# MKR1000.net
KiCad netlist of a schematic drawn in EAGLE
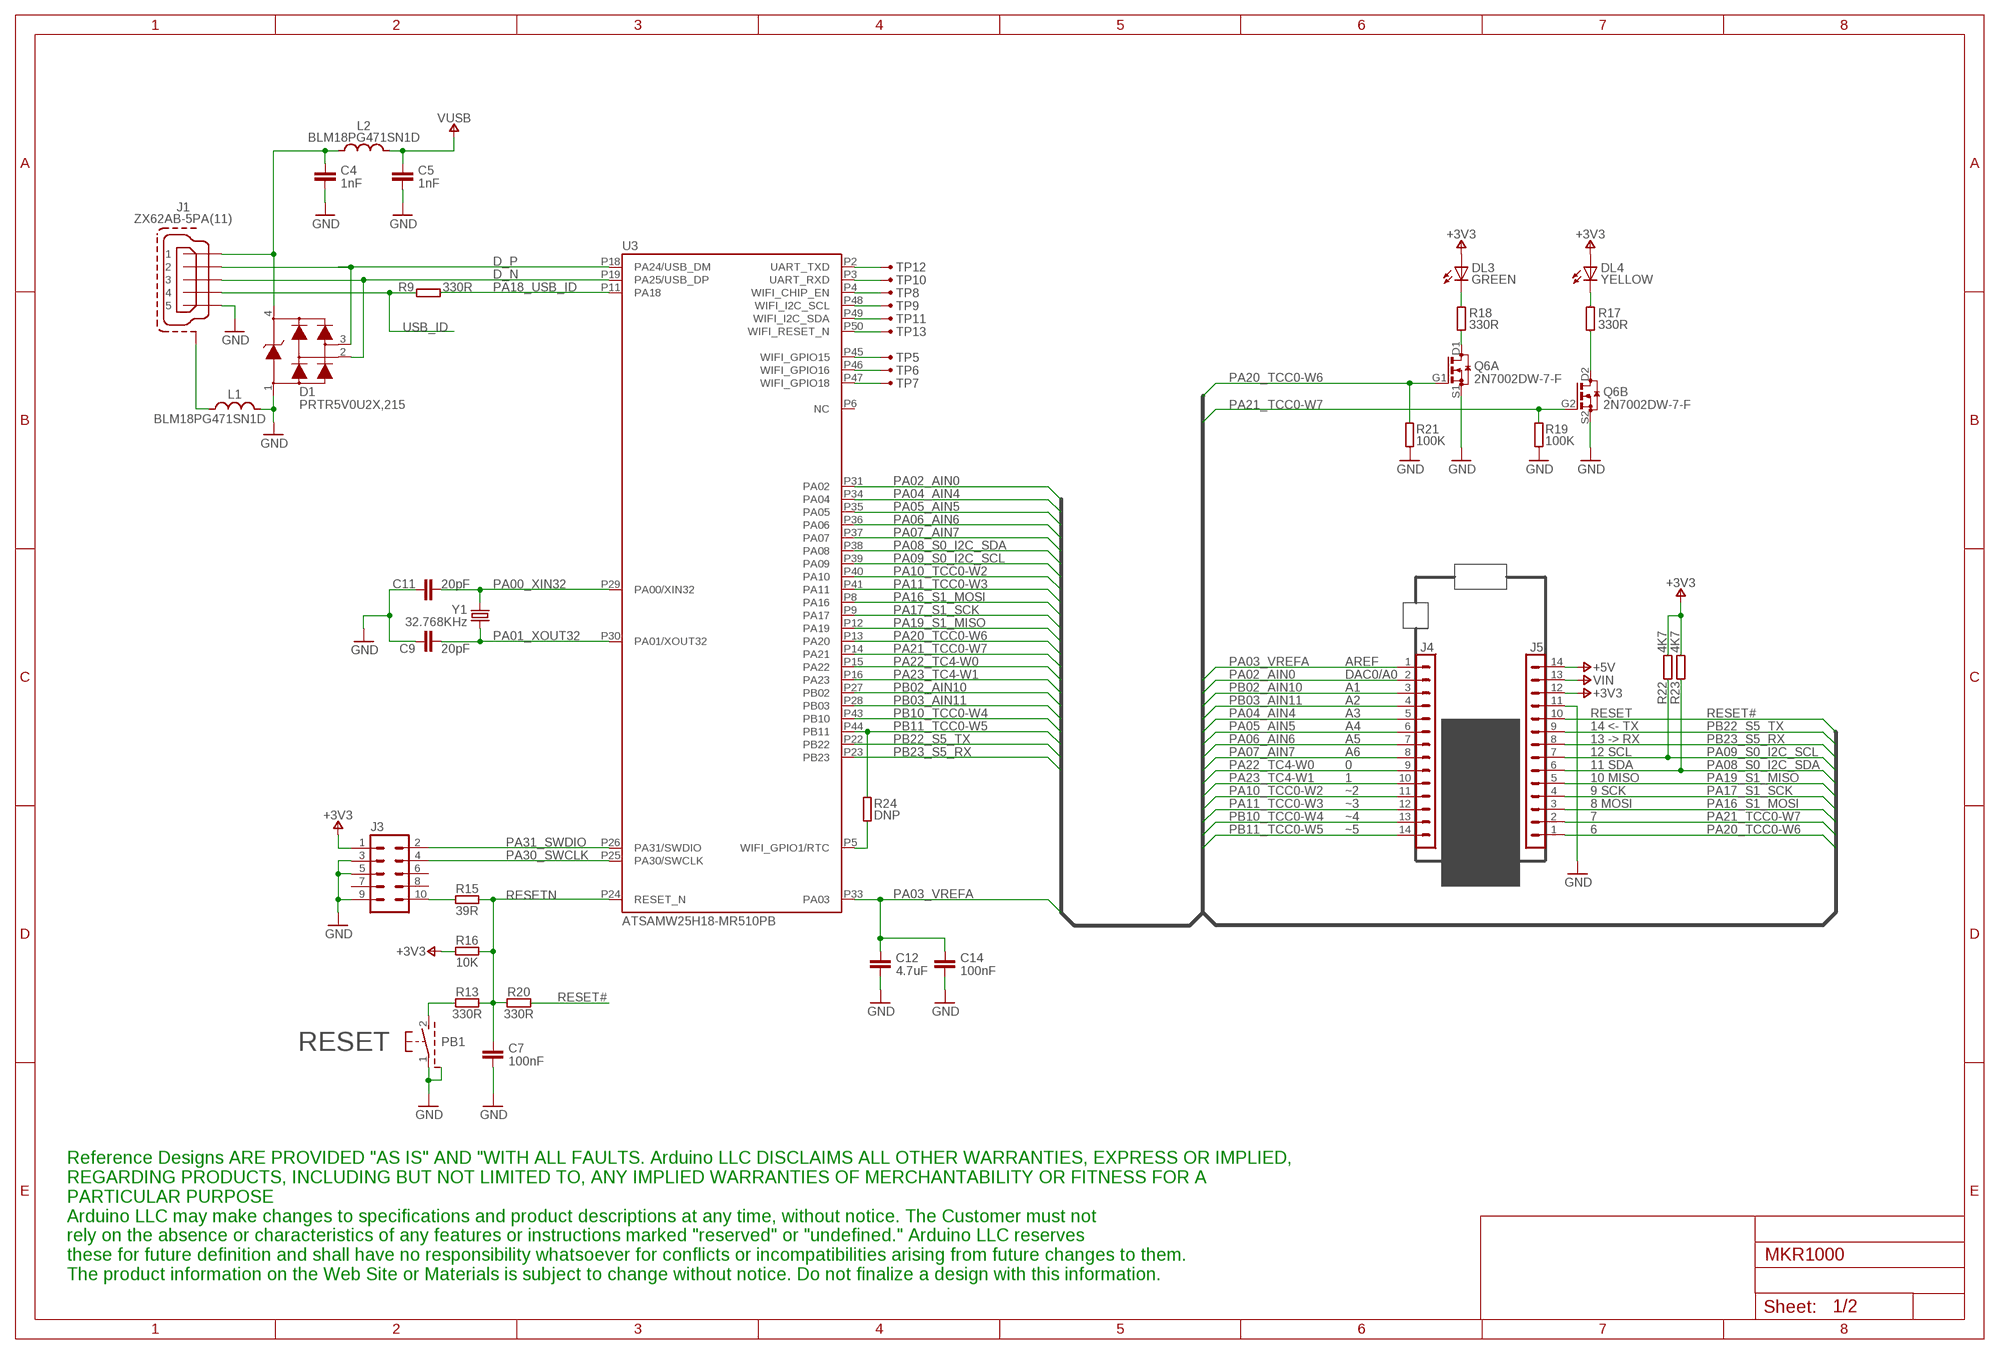
[diagram p0: schematic, sheet 1]
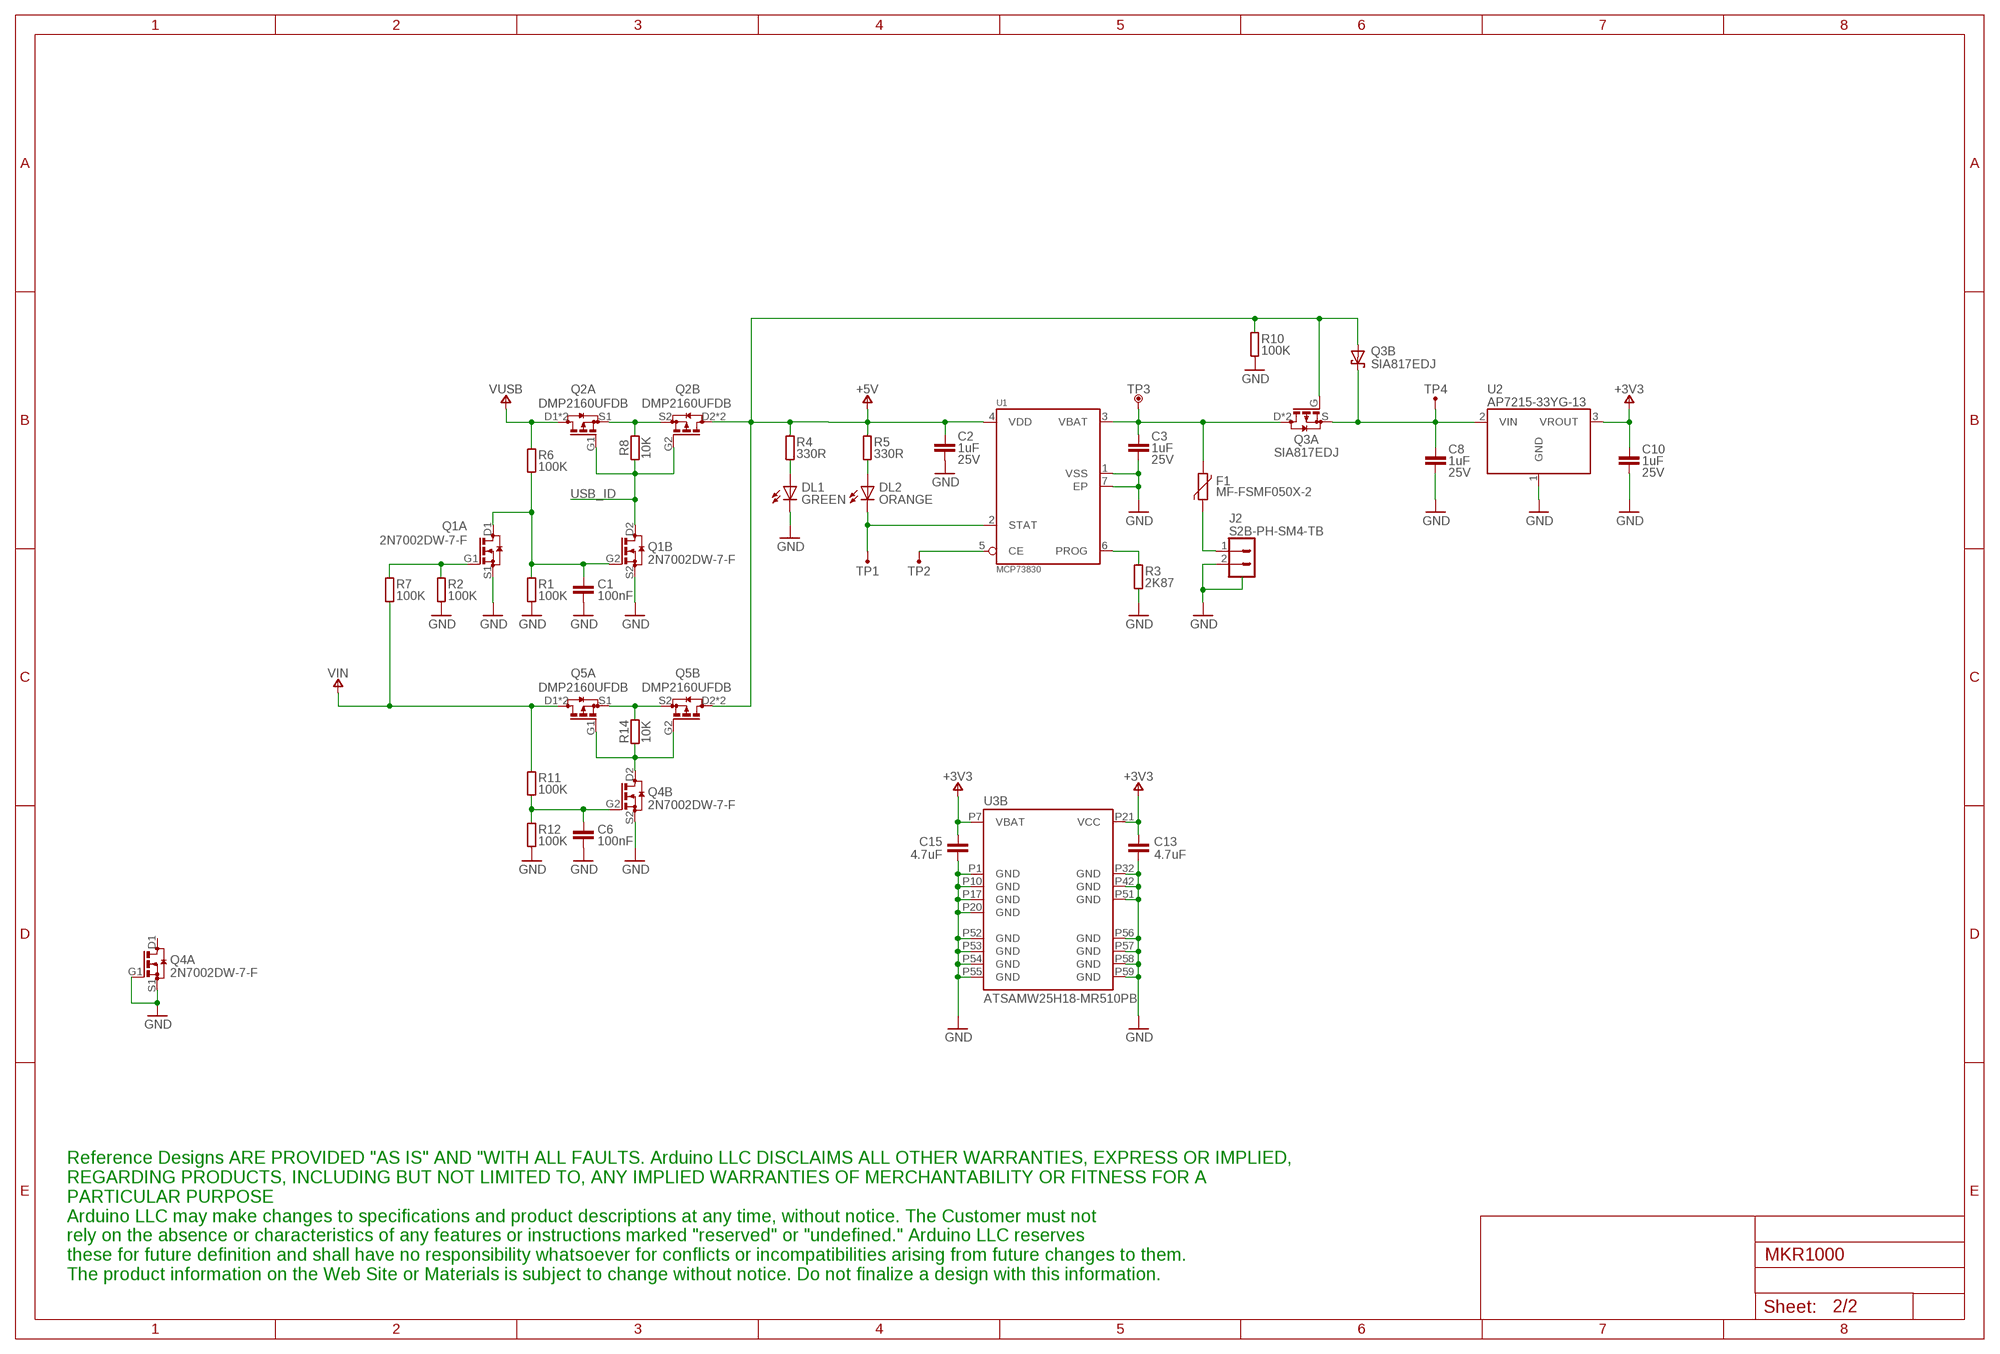
[diagram p1: schematic, sheet 2]

(export (version "E")
  (design (tool "Eeschema 10.0.6"))
  (components
    (comp (ref "C4")
      (value "1nF")
      (footprint "eagle-import:0402-1005X55N")
      (fields (field (name "MF") "Samsung") (field (name "MPN") "CL05B102KB5NNNC "))
      (libsource (lib "eagle-import") (part "C-0402-1NF"))
    )
    (comp (ref "C5")
      (value "1nF")
      (footprint "eagle-import:0402-1005X55N")
      (fields (field (name "MF") "Samsung") (field (name "MPN") "CL05B102KB5NNNC "))
      (libsource (lib "eagle-import") (part "C-0402-1NF"))
    )
    (comp (ref "C7")
      (value "100nF")
      (footprint "eagle-import:0402-1005X55N")
      (fields (field (name "MF") "TDK") (field (name "MPN") "C1005X5R1H104K050BB "))
      (libsource (lib "eagle-import") (part "C-0402-100NF"))
    )
    (comp (ref "C9")
      (value "20pF")
      (footprint "eagle-import:0402-1005X55N")
      (fields (field (name "MF") "Kemet") (field (name "MPN") "CBR04C200J5GAC "))
      (libsource (lib "eagle-import") (part "C-0402-20PF"))
    )
    (comp (ref "C11")
      (value "20pF")
      (footprint "eagle-import:0402-1005X55N")
      (fields (field (name "MF") "Kemet") (field (name "MPN") "CBR04C200J5GAC "))
      (libsource (lib "eagle-import") (part "C-0402-20PF"))
    )
    (comp (ref "C12")
      (value "4.7uF")
      (footprint "eagle-import:0402-1005X55N")
      (fields (field (name "MF") "Murata") (field (name "MPN") "GRM155R60J475ME47D "))
      (libsource (lib "eagle-import") (part "C-0402-4.7UF"))
    )
    (comp (ref "C14")
      (value "100nF")
      (footprint "eagle-import:0402-1005X55N")
      (fields (field (name "MF") "TDK") (field (name "MPN") "C1005X5R1H104K050BB "))
      (libsource (lib "eagle-import") (part "C-0402-100NF"))
    )
    (comp (ref "D1")
      (value "PRTR5V0U2X,215")
      (footprint "eagle-import:SOT190P230X110-4N")
      (fields (field (name "MF") "NXP") (field (name "MPN") "PRTR5V0U2X,215 "))
      (libsource (lib "eagle-import") (part "PRTR5V0U2X,215"))
    )
    (comp (ref "DL3")
      (value "GREEN")
      (footprint "eagle-import:LEDC1608X80N-AK")
      (fields (field (name "MF") "Avago ") (field (name "MPN") "HSMG-C190 "))
      (libsource (lib "eagle-import") (part "LED-0603-GREEN"))
    )
    (comp (ref "DL4")
      (value "YELLOW")
      (footprint "eagle-import:LEDC1608X80N-AK")
      (fields (field (name "MF") "Avago") (field (name "MPN") "HSMY-C190"))
      (libsource (lib "eagle-import") (part "LED-0603-YELLOW"))
    )
    (comp (ref "J1")
      (value "ZX62AB-5PA(11)")
      (footprint "eagle-import:USBMICRO-ZX62-AB-5PA")
      (libsource (lib "eagle-import") (part "ZX62AB-5PA(11)"))
    )
    (comp (ref "J3")
      (value "M50-3600542")
      (footprint "eagle-import:FCI-MINITEK127HDR-10")
      (fields (field (name "MF") "Harwin") (field (name "MPN") "M50-3600542 "))
      (libsource (lib "eagle-import") (part "M50-3600542"))
    )
    (comp (ref "J4")
      (value "DNP")
      (footprint "eagle-import:STRIP-14-MODULI-A11")
      (libsource (lib "eagle-import") (part "STRIP-14"))
    )
    (comp (ref "J5")
      (value "DNP")
      (footprint "eagle-import:STRIP-14-MODULI-A11")
      (libsource (lib "eagle-import") (part "STRIP-14"))
    )
    (comp (ref "L1")
      (value "BLM18PG471SN1D")
      (footprint "eagle-import:0603-1608X90N")
      (libsource (lib "eagle-import") (part "BLM18PG471SN1D"))
    )
    (comp (ref "L2")
      (value "BLM18PG471SN1D")
      (footprint "eagle-import:0603-1608X90N")
      (libsource (lib "eagle-import") (part "BLM18PG471SN1D"))
    )
    (comp (ref "PB1")
      (value "PTS820-20MM")
      (footprint "eagle-import:PULS-45X29-PST820")
      (fields (field (name "MF") "C&K"))
      (libsource (lib "eagle-import") (part "PTS820-20MM"))
    )
    (comp (ref "Q6")
      (value "2N7002DW-7-F")
      (footprint "eagle-import:SOT65P210X110-6AN-DM")
      (fields (field (name "MF") "Diodes Inc ") (field (name "MPN") "2N7002DW-7-F "))
      (libsource (lib "eagle-import") (part "2N7002DW-7-F"))
    )
    (comp (ref "R9")
      (value "330R")
      (footprint "eagle-import:0402-1005X55N")
      (fields (field (name "MF") "Yageo ") (field (name "MPN") "RC0402FR-07330RL "))
      (libsource (lib "eagle-import") (part "R-0402-330R"))
    )
    (comp (ref "R13")
      (value "330R")
      (footprint "eagle-import:0402-1005X55N")
      (fields (field (name "MF") "Yageo ") (field (name "MPN") "RC0402FR-07330RL "))
      (libsource (lib "eagle-import") (part "R-0402-330R"))
    )
    (comp (ref "R15")
      (value "39R")
      (footprint "eagle-import:0402-1005X55N")
      (fields (field (name "MF") "Yageo ") (field (name "MPN") "RC0402FR-0739RL "))
      (libsource (lib "eagle-import") (part "R-0402-39R"))
    )
    (comp (ref "R16")
      (value "10K")
      (footprint "eagle-import:0402-1005X55N")
      (fields (field (name "MF") "Yageo") (field (name "MPN") "RC0402FR-0710KL"))
      (libsource (lib "eagle-import") (part "R-0402-10K"))
    )
    (comp (ref "R17")
      (value "330R")
      (footprint "eagle-import:0402-1005X55N")
      (fields (field (name "MF") "Yageo ") (field (name "MPN") "RC0402FR-07330RL "))
      (libsource (lib "eagle-import") (part "R-0402-330R"))
    )
    (comp (ref "R18")
      (value "330R")
      (footprint "eagle-import:0402-1005X55N")
      (fields (field (name "MF") "Yageo ") (field (name "MPN") "RC0402FR-07330RL "))
      (libsource (lib "eagle-import") (part "R-0402-330R"))
    )
    (comp (ref "R19")
      (value "100K")
      (footprint "eagle-import:0402-1005X55N")
      (fields (field (name "MF") "Yageo ") (field (name "MPN") "RC0402FR-07100KL "))
      (libsource (lib "eagle-import") (part "R-0402-100K"))
    )
    (comp (ref "R20")
      (value "330R")
      (footprint "eagle-import:0402-1005X55N")
      (fields (field (name "MF") "Yageo ") (field (name "MPN") "RC0402FR-07330RL "))
      (libsource (lib "eagle-import") (part "R-0402-330R"))
    )
    (comp (ref "R21")
      (value "100K")
      (footprint "eagle-import:0402-1005X55N")
      (fields (field (name "MF") "Yageo ") (field (name "MPN") "RC0402FR-07100KL "))
      (libsource (lib "eagle-import") (part "R-0402-100K"))
    )
    (comp (ref "R22")
      (value "4K7")
      (footprint "eagle-import:0402-1005X55N")
      (fields (field (name "MF") "Yageo ") (field (name "MPN") "RC0402FR-074K7L "))
      (libsource (lib "eagle-import") (part "R-0402-4K7"))
    )
    (comp (ref "R23")
      (value "4K7")
      (footprint "eagle-import:0402-1005X55N")
      (fields (field (name "MF") "Yageo ") (field (name "MPN") "RC0402FR-074K7L "))
      (libsource (lib "eagle-import") (part "R-0402-4K7"))
    )
    (comp (ref "R24")
      (value "DNP")
      (footprint "eagle-import:0402-1005X55N")
      (libsource (lib "eagle-import") (part "R-0402-DNP"))
    )
    (comp (ref "TP5")
      (value "TESTPAD")
      (footprint "eagle-import:PAD-SMD")
      (libsource (lib "eagle-import") (part "TESTPAD"))
    )
    (comp (ref "TP6")
      (value "TESTPAD")
      (footprint "eagle-import:PAD-SMD")
      (libsource (lib "eagle-import") (part "TESTPAD"))
    )
    (comp (ref "TP7")
      (value "TESTPAD")
      (footprint "eagle-import:PAD-SMD")
      (libsource (lib "eagle-import") (part "TESTPAD"))
    )
    (comp (ref "TP8")
      (value "TESTPAD")
      (footprint "eagle-import:PAD-SMD")
      (libsource (lib "eagle-import") (part "TESTPAD"))
    )
    (comp (ref "TP9")
      (value "TESTPAD")
      (footprint "eagle-import:PAD-SMD")
      (libsource (lib "eagle-import") (part "TESTPAD"))
    )
    (comp (ref "TP10")
      (value "TESTPAD")
      (footprint "eagle-import:PAD-SMD")
      (libsource (lib "eagle-import") (part "TESTPAD"))
    )
    (comp (ref "TP11")
      (value "TESTPAD")
      (footprint "eagle-import:PAD-SMD")
      (libsource (lib "eagle-import") (part "TESTPAD"))
    )
    (comp (ref "TP12")
      (value "TESTPAD")
      (footprint "eagle-import:PAD-SMD")
      (libsource (lib "eagle-import") (part "TESTPAD"))
    )
    (comp (ref "TP13")
      (value "TESTPAD")
      (footprint "eagle-import:PAD-SMD")
      (libsource (lib "eagle-import") (part "TESTPAD"))
    )
    (comp (ref "U3")
      (value "ATSAMW25H18-MR510PB")
      (footprint "eagle-import:SAMW25")
      (fields (field (name "MF") "Atmel"))
      (libsource (lib "eagle-import") (part "ATSAMW25H18-MR510PB"))
    )
    (comp (ref "Y1")
      (value "32.768KHz")
      (footprint "eagle-import:QUARZO-ABS07")
      (fields (field (name "MF") "Abracon ") (field (name "MPN") "ABS07-32.768KHZ-T "))
      (libsource (lib "eagle-import") (part "ABS07-32.768KHZ-T"))
    )
    (comp (ref "C1")
      (value "100nF")
      (footprint "eagle-import:0402-1005X55N")
      (fields (field (name "MF") "TDK") (field (name "MPN") "C1005X5R1H104K050BB "))
      (libsource (lib "eagle-import") (part "C-0402-100NF"))
    )
    (comp (ref "C2")
      (value "1uF")
      (footprint "eagle-import:0402-1005X55N")
      (fields
        (field (name "MF") "Murata")
        (field (name "MPN") "GRM155R61E105KA12D ")
        (field (name "VOLTAGE") "25V")
      )
      (libsource (lib "eagle-import") (part "C-0402-1UF"))
    )
    (comp (ref "C3")
      (value "1uF")
      (footprint "eagle-import:0402-1005X55N")
      (fields
        (field (name "MF") "Murata")
        (field (name "MPN") "GRM155R61E105KA12D ")
        (field (name "VOLTAGE") "25V")
      )
      (libsource (lib "eagle-import") (part "C-0402-1UF"))
    )
    (comp (ref "C6")
      (value "100nF")
      (footprint "eagle-import:0402-1005X55N")
      (fields (field (name "MF") "TDK") (field (name "MPN") "C1005X5R1H104K050BB "))
      (libsource (lib "eagle-import") (part "C-0402-100NF"))
    )
    (comp (ref "C8")
      (value "1uF")
      (footprint "eagle-import:0402-1005X55N")
      (fields
        (field (name "MF") "Murata")
        (field (name "MPN") "GRM155R61E105KA12D ")
        (field (name "VOLTAGE") "25V")
      )
      (libsource (lib "eagle-import") (part "C-0402-1UF"))
    )
    (comp (ref "C10")
      (value "1uF")
      (footprint "eagle-import:0402-1005X55N")
      (fields
        (field (name "MF") "Murata")
        (field (name "MPN") "GRM155R61E105KA12D ")
        (field (name "VOLTAGE") "25V")
      )
      (libsource (lib "eagle-import") (part "C-0402-1UF"))
    )
    (comp (ref "C13")
      (value "4.7uF")
      (footprint "eagle-import:0402-1005X55N")
      (fields (field (name "MF") "Murata") (field (name "MPN") "GRM155R60J475ME47D "))
      (libsource (lib "eagle-import") (part "C-0402-4.7UF"))
    )
    (comp (ref "C15")
      (value "4.7uF")
      (footprint "eagle-import:0402-1005X55N")
      (fields (field (name "MF") "Murata") (field (name "MPN") "GRM155R60J475ME47D "))
      (libsource (lib "eagle-import") (part "C-0402-4.7UF"))
    )
    (comp (ref "DL1")
      (value "GREEN")
      (footprint "eagle-import:LEDC1608X80N-AK")
      (fields (field (name "MF") "Avago ") (field (name "MPN") "HSMG-C190 "))
      (libsource (lib "eagle-import") (part "LED-0603-GREEN"))
    )
    (comp (ref "DL2")
      (value "ORANGE")
      (footprint "eagle-import:LEDC1608X80N-AK")
      (fields (field (name "MF") "Avago ") (field (name "MPN") "HSMD-C190 "))
      (libsource (lib "eagle-import") (part "LED-0603-ORANGE"))
    )
    (comp (ref "F1")
      (value "MF-FSMF050X-2")
      (footprint "eagle-import:0603-F1608X100N")
      (fields (field (name "MF") "Bourns Inc ") (field (name "MPN") "MF-FSMF050X-2 "))
      (libsource (lib "eagle-import") (part "MF-FSMF050X-2"))
    )
    (comp (ref "J2")
      (value "S2B-PH-SM4-TB")
      (footprint "eagle-import:JST-S2B-PH-SM4-TB")
      (fields (field (name "MF") "JST ") (field (name "MPN") "S2B-PH-SM4-TB(LF)(SN) "))
      (libsource (lib "eagle-import") (part "S2B-PH-SM4-TB"))
    )
    (comp (ref "Q1")
      (value "2N7002DW-7-F")
      (footprint "eagle-import:SOT65P210X110-6AN-DM")
      (fields (field (name "MF") "Diodes Inc ") (field (name "MPN") "2N7002DW-7-F "))
      (libsource (lib "eagle-import") (part "2N7002DW-7-F"))
    )
    (comp (ref "Q2")
      (value "DMP2160UFDB")
      (footprint "eagle-import:SON65P200X200X60-8N-DM")
      (fields (field (name "MF") "Diodes Inc ") (field (name "MPN") "DMP2160UFDB-7 "))
      (libsource (lib "eagle-import") (part "DMP2160UFDB"))
    )
    (comp (ref "Q3")
      (value "SIA817EDJ")
      (footprint "eagle-import:SON65P205X205X75-8N-MWSD")
      (fields (field (name "MF") "Vishay ") (field (name "MPN") "SIA817EDJ-T1-GE3 "))
      (libsource (lib "eagle-import") (part "SIA817EDJ"))
    )
    (comp (ref "Q4")
      (value "2N7002DW-7-F")
      (footprint "eagle-import:SOT65P210X110-6AN-DM")
      (fields (field (name "MF") "Diodes Inc ") (field (name "MPN") "2N7002DW-7-F "))
      (libsource (lib "eagle-import") (part "2N7002DW-7-F"))
    )
    (comp (ref "Q5")
      (value "DMP2160UFDB")
      (footprint "eagle-import:SON65P200X200X60-8N-DM")
      (fields (field (name "MF") "Diodes Inc ") (field (name "MPN") "DMP2160UFDB-7 "))
      (libsource (lib "eagle-import") (part "DMP2160UFDB"))
    )
    (comp (ref "R1")
      (value "100K")
      (footprint "eagle-import:0402-1005X55N")
      (fields (field (name "MF") "Yageo ") (field (name "MPN") "RC0402FR-07100KL "))
      (libsource (lib "eagle-import") (part "R-0402-100K"))
    )
    (comp (ref "R2")
      (value "100K")
      (footprint "eagle-import:0402-1005X55N")
      (fields (field (name "MF") "Yageo ") (field (name "MPN") "RC0402FR-07100KL "))
      (libsource (lib "eagle-import") (part "R-0402-100K"))
    )
    (comp (ref "R3")
      (value "2K87")
      (footprint "eagle-import:0805-R2013X50N")
      (fields (field (name "MF") "Panasonic ") (field (name "MPN") "ERJ6ENF2871V "))
      (libsource (lib "eagle-import") (part "R-0805-2K87"))
    )
    (comp (ref "R4")
      (value "330R")
      (footprint "eagle-import:0402-1005X55N")
      (fields (field (name "MF") "Yageo ") (field (name "MPN") "RC0402FR-07330RL "))
      (libsource (lib "eagle-import") (part "R-0402-330R"))
    )
    (comp (ref "R5")
      (value "330R")
      (footprint "eagle-import:0402-1005X55N")
      (fields (field (name "MF") "Yageo ") (field (name "MPN") "RC0402FR-07330RL "))
      (libsource (lib "eagle-import") (part "R-0402-330R"))
    )
    (comp (ref "R6")
      (value "100K")
      (footprint "eagle-import:0402-1005X55N")
      (fields (field (name "MF") "Yageo ") (field (name "MPN") "RC0402FR-07100KL "))
      (libsource (lib "eagle-import") (part "R-0402-100K"))
    )
    (comp (ref "R7")
      (value "100K")
      (footprint "eagle-import:0402-1005X55N")
      (fields (field (name "MF") "Yageo ") (field (name "MPN") "RC0402FR-07100KL "))
      (libsource (lib "eagle-import") (part "R-0402-100K"))
    )
    (comp (ref "R8")
      (value "10K")
      (footprint "eagle-import:0402-1005X55N")
      (fields (field (name "MF") "Yageo") (field (name "MPN") "RC0402FR-0710KL"))
      (libsource (lib "eagle-import") (part "R-0402-10K"))
    )
    (comp (ref "R10")
      (value "100K")
      (footprint "eagle-import:0402-1005X55N")
      (fields (field (name "MF") "Yageo ") (field (name "MPN") "RC0402FR-07100KL "))
      (libsource (lib "eagle-import") (part "R-0402-100K"))
    )
    (comp (ref "R11")
      (value "100K")
      (footprint "eagle-import:0402-1005X55N")
      (fields (field (name "MF") "Yageo ") (field (name "MPN") "RC0402FR-07100KL "))
      (libsource (lib "eagle-import") (part "R-0402-100K"))
    )
    (comp (ref "R12")
      (value "100K")
      (footprint "eagle-import:0402-1005X55N")
      (fields (field (name "MF") "Yageo ") (field (name "MPN") "RC0402FR-07100KL "))
      (libsource (lib "eagle-import") (part "R-0402-100K"))
    )
    (comp (ref "R14")
      (value "10K")
      (footprint "eagle-import:0402-1005X55N")
      (fields (field (name "MF") "Yageo") (field (name "MPN") "RC0402FR-0710KL"))
      (libsource (lib "eagle-import") (part "R-0402-10K"))
    )
    (comp (ref "TP1")
      (value "TESTPAD")
      (footprint "eagle-import:PAD-SMD")
      (libsource (lib "eagle-import") (part "TESTPAD"))
    )
    (comp (ref "TP2")
      (value "TESTPAD")
      (footprint "eagle-import:PAD-SMD")
      (libsource (lib "eagle-import") (part "TESTPAD"))
    )
    (comp (ref "TP3")
      (value "TESTPOINT")
      (footprint "eagle-import:TESTPOINT-60MLS-F0_9MM")
      (libsource (lib "eagle-import") (part "TESTPOINT"))
    )
    (comp (ref "TP4")
      (value "TESTPAD")
      (footprint "eagle-import:PAD-SMD")
      (libsource (lib "eagle-import") (part "TESTPAD"))
    )
    (comp (ref "U1")
      (value "MCP73830")
      (footprint "eagle-import:SON50P200X200X80-7N-EP160X60")
      (fields (field (name "MF") "Microchip ") (field (name "MPN") "MCP73830T-2AAI/MYY "))
      (libsource (lib "eagle-import") (part "MCP73830"))
    )
    (comp (ref "U2")
      (value "AP7215-33YG-13")
      (footprint "eagle-import:SOT150P400X160-3N")
      (fields (field (name "MF") "Diodes Inc ") (field (name "MPN") "AP7215-33YG-13 "))
      (libsource (lib "eagle-import") (part "AP7215-33YG-13"))
    )
  )
  (nets
    (net (code "1") (name "+3V3") (class "Default")
      (node (ref "C10") (pin "1") (pinfunction "1_1") (pintype "passive"))
      (node (ref "C13") (pin "1") (pinfunction "1_1") (pintype "passive"))
      (node (ref "C15") (pin "1") (pinfunction "1_1") (pintype "passive"))
      (node (ref "DL3") (pin "A") (pinfunction "A_A") (pintype "passive"))
      (node (ref "DL4") (pin "A") (pinfunction "A_A") (pintype "passive"))
      (node (ref "J3") (pin "1") (pinfunction "1_1") (pintype "passive"))
      (node (ref "J5") (pin "12") (pinfunction "12_12") (pintype "passive"))
      (node (ref "R16") (pin "1") (pinfunction "1_1") (pintype "passive"))
      (node (ref "R22") (pin "2") (pinfunction "2_2") (pintype "passive"))
      (node (ref "R23") (pin "2") (pinfunction "2_2") (pintype "passive"))
      (node (ref "U2") (pin "3") (pinfunction "VROUT_3") (pintype "power_in"))
      (node (ref "U3") (pin "P21") (pinfunction "VCC_P21") (pintype "power_in"))
      (node (ref "U3") (pin "P7") (pinfunction "VBAT_P7") (pintype "power_in"))
    )
    (net (code "2") (name "+5V") (class "Default")
      (node (ref "C2") (pin "1") (pinfunction "1_1") (pintype "passive"))
      (node (ref "J5") (pin "14") (pinfunction "14_14") (pintype "passive"))
      (node (ref "Q2") (pin "D2") (pinfunction "D_D2") (pintype "passive"))
      (node (ref "Q2") (pin "D2'") (pinfunction "D_D2'") (pintype "passive"))
      (node (ref "Q3") (pin "A") (pinfunction "A_A") (pintype "passive"))
      (node (ref "Q3") (pin "G") (pinfunction "G_G") (pintype "passive"))
      (node (ref "Q5") (pin "D2") (pinfunction "D_D2") (pintype "passive"))
      (node (ref "Q5") (pin "D2'") (pinfunction "D_D2'") (pintype "passive"))
      (node (ref "R10") (pin "2") (pinfunction "2_2") (pintype "passive"))
      (node (ref "R4") (pin "2") (pinfunction "2_2") (pintype "passive"))
      (node (ref "R5") (pin "2") (pinfunction "2_2") (pintype "passive"))
      (node (ref "U1") (pin "4") (pinfunction "VDD_4") (pintype "power_in"))
    )
    (net (code "3") (name "D_N") (class "Default")
      (node (ref "D1") (pin "2") (pinfunction "2_2") (pintype "passive"))
      (node (ref "J1") (pin "3") (pinfunction "3_3") (pintype "passive"))
      (node (ref "U3") (pin "P19") (pinfunction "PA25/USB_DP_P19") (pintype "bidirectional"))
    )
    (net (code "4") (name "D_P") (class "Default")
      (node (ref "D1") (pin "3") (pinfunction "3_3") (pintype "passive"))
      (node (ref "J1") (pin "2") (pinfunction "2_2") (pintype "passive"))
      (node (ref "U3") (pin "P18") (pinfunction "PA24/USB_DM_P18") (pintype "bidirectional"))
    )
    (net (code "5") (name "GND") (class "Default")
      (node (ref "C1") (pin "2") (pinfunction "2_2") (pintype "passive"))
      (node (ref "C10") (pin "2") (pinfunction "2_2") (pintype "passive"))
      (node (ref "C11") (pin "1") (pinfunction "1_1") (pintype "passive"))
      (node (ref "C12") (pin "2") (pinfunction "2_2") (pintype "passive"))
      (node (ref "C13") (pin "2") (pinfunction "2_2") (pintype "passive"))
      (node (ref "C14") (pin "2") (pinfunction "2_2") (pintype "passive"))
      (node (ref "C15") (pin "2") (pinfunction "2_2") (pintype "passive"))
      (node (ref "C2") (pin "2") (pinfunction "2_2") (pintype "passive"))
      (node (ref "C3") (pin "2") (pinfunction "2_2") (pintype "passive"))
      (node (ref "C4") (pin "2") (pinfunction "2_2") (pintype "passive"))
      (node (ref "C5") (pin "2") (pinfunction "2_2") (pintype "passive"))
      (node (ref "C6") (pin "2") (pinfunction "2_2") (pintype "passive"))
      (node (ref "C7") (pin "2") (pinfunction "2_2") (pintype "passive"))
      (node (ref "C8") (pin "2") (pinfunction "2_2") (pintype "passive"))
      (node (ref "C9") (pin "1") (pinfunction "1_1") (pintype "passive"))
      (node (ref "D1") (pin "1") (pinfunction "1_1") (pintype "passive"))
      (node (ref "DL1") (pin "C") (pinfunction "C_C") (pintype "passive"))
      (node (ref "J1") (pin "5") (pinfunction "5_5") (pintype "passive"))
      (node (ref "J2") (pin "2") (pinfunction "2_2") (pintype "passive"))
      (node (ref "J2") (pin "3") (pinfunction "SH_3") (pintype "passive"))
      (node (ref "J2") (pin "4") (pinfunction "SH_4") (pintype "passive"))
      (node (ref "J3") (pin "3") (pinfunction "3_3") (pintype "passive"))
      (node (ref "J3") (pin "5") (pinfunction "5_5") (pintype "passive"))
      (node (ref "J3") (pin "9") (pinfunction "9_9") (pintype "passive"))
      (node (ref "J5") (pin "11") (pinfunction "11_11") (pintype "passive"))
      (node (ref "L1") (pin "2") (pinfunction "2_2") (pintype "passive"))
      (node (ref "PB1") (pin "1") (pinfunction "P_1") (pintype "passive"))
      (node (ref "PB1") (pin "3") (pinfunction "SH_3") (pintype "passive"))
      (node (ref "PB1") (pin "4") (pinfunction "SH_4") (pintype "passive"))
      (node (ref "PB1") (pin "5") (pinfunction "SH_5") (pintype "passive"))
      (node (ref "PB1") (pin "6") (pinfunction "SH_6") (pintype "passive"))
      (node (ref "Q1") (pin "S1") (pinfunction "S_S1") (pintype "passive"))
      (node (ref "Q1") (pin "S2") (pinfunction "S_S2") (pintype "passive"))
      (node (ref "Q4") (pin "G1") (pinfunction "G_G1") (pintype "passive"))
      (node (ref "Q4") (pin "S1") (pinfunction "S_S1") (pintype "passive"))
      (node (ref "Q4") (pin "S2") (pinfunction "S_S2") (pintype "passive"))
      (node (ref "Q6") (pin "S1") (pinfunction "S_S1") (pintype "passive"))
      (node (ref "Q6") (pin "S2") (pinfunction "S_S2") (pintype "passive"))
      (node (ref "R1") (pin "1") (pinfunction "1_1") (pintype "passive"))
      (node (ref "R10") (pin "1") (pinfunction "1_1") (pintype "passive"))
      (node (ref "R12") (pin "1") (pinfunction "1_1") (pintype "passive"))
      (node (ref "R19") (pin "1") (pinfunction "1_1") (pintype "passive"))
      (node (ref "R2") (pin "1") (pinfunction "1_1") (pintype "passive"))
      (node (ref "R21") (pin "1") (pinfunction "1_1") (pintype "passive"))
      (node (ref "R3") (pin "1") (pinfunction "1_1") (pintype "passive"))
      (node (ref "U1") (pin "1") (pinfunction "VSS_1") (pintype "power_in"))
      (node (ref "U1") (pin "7") (pinfunction "EP_7") (pintype "passive"))
      (node (ref "U2") (pin "1") (pinfunction "GND_1") (pintype "power_in"))
      (node (ref "U3") (pin "P1") (pinfunction "GND_P1") (pintype "power_in"))
      (node (ref "U3") (pin "P10") (pinfunction "GND_P10") (pintype "power_in"))
      (node (ref "U3") (pin "P17") (pinfunction "GND_P17") (pintype "power_in"))
      (node (ref "U3") (pin "P20") (pinfunction "GND_P20") (pintype "power_in"))
      (node (ref "U3") (pin "P32") (pinfunction "GND_P32") (pintype "power_in"))
      (node (ref "U3") (pin "P42") (pinfunction "GND_P42") (pintype "power_in"))
      (node (ref "U3") (pin "P51") (pinfunction "GND_P51") (pintype "power_in"))
      (node (ref "U3") (pin "P52") (pinfunction "GND_P52") (pintype "power_in"))
      (node (ref "U3") (pin "P53") (pinfunction "GND_P53") (pintype "power_in"))
      (node (ref "U3") (pin "P54") (pinfunction "GND_P54") (pintype "power_in"))
      (node (ref "U3") (pin "P55") (pinfunction "GND_P55") (pintype "power_in"))
      (node (ref "U3") (pin "P56") (pinfunction "GND_P56") (pintype "power_in"))
      (node (ref "U3") (pin "P57") (pinfunction "GND_P57") (pintype "power_in"))
      (node (ref "U3") (pin "P58") (pinfunction "GND_P58") (pintype "power_in"))
      (node (ref "U3") (pin "P59") (pinfunction "GND_P59") (pintype "power_in"))
    )
    (net (code "6") (name "Net-(C4-Pad1)") (class "Default")
      (node (ref "C4") (pin "1") (pinfunction "1_1") (pintype "passive"))
      (node (ref "D1") (pin "4") (pinfunction "4_4") (pintype "passive"))
      (node (ref "J1") (pin "1") (pinfunction "1_1") (pintype "passive"))
      (node (ref "L2") (pin "1") (pinfunction "1_1") (pintype "passive"))
    )
    (net (code "7") (name "Net-(DL1-PadA)") (class "Default")
      (node (ref "DL1") (pin "A") (pinfunction "A_A") (pintype "passive"))
      (node (ref "R4") (pin "1") (pinfunction "1_1") (pintype "passive"))
    )
    (net (code "8") (name "Net-(DL2-PadA)") (class "Default")
      (node (ref "DL2") (pin "A") (pinfunction "A_A") (pintype "passive"))
      (node (ref "R5") (pin "1") (pinfunction "1_1") (pintype "passive"))
    )
    (net (code "9") (name "Net-(DL3-PadC)") (class "Default")
      (node (ref "DL3") (pin "C") (pinfunction "C_C") (pintype "passive"))
      (node (ref "R18") (pin "2") (pinfunction "2_2") (pintype "passive"))
    )
    (net (code "10") (name "Net-(DL4-PadC)") (class "Default")
      (node (ref "DL4") (pin "C") (pinfunction "C_C") (pintype "passive"))
      (node (ref "R17") (pin "2") (pinfunction "2_2") (pintype "passive"))
    )
    (net (code "11") (name "Net-(F1-Pad1)") (class "Default")
      (node (ref "F1") (pin "1") (pinfunction "1_1") (pintype "passive"))
      (node (ref "J2") (pin "1") (pinfunction "1_1") (pintype "passive"))
    )
    (net (code "12") (name "Net-(J1-SH-Pad10)") (class "Default")
      (node (ref "J1") (pin "10") (pinfunction "SH_10") (pintype "passive"))
      (node (ref "J1") (pin "11") (pinfunction "SH_11") (pintype "passive"))
      (node (ref "J1") (pin "6") (pinfunction "SH_6") (pintype "passive"))
      (node (ref "J1") (pin "7") (pinfunction "SH_7") (pintype "passive"))
      (node (ref "J1") (pin "8") (pinfunction "SH_8") (pintype "passive"))
      (node (ref "J1") (pin "9") (pinfunction "SH_9") (pintype "passive"))
      (node (ref "L1") (pin "1") (pinfunction "1_1") (pintype "passive"))
    )
    (net (code "13") (name "Net-(J3-Pad10)") (class "Default")
      (node (ref "J3") (pin "10") (pinfunction "10_10") (pintype "passive"))
      (node (ref "R15") (pin "1") (pinfunction "1_1") (pintype "passive"))
    )
    (net (code "14") (name "Net-(PB1-S)") (class "Default")
      (node (ref "PB1") (pin "2") (pinfunction "S_2") (pintype "passive"))
      (node (ref "R13") (pin "1") (pinfunction "1_1") (pintype "passive"))
    )
    (net (code "15") (name "Net-(Q1A-D)") (class "Default")
      (node (ref "C1") (pin "1") (pinfunction "1_1") (pintype "passive"))
      (node (ref "Q1") (pin "D1") (pinfunction "D_D1") (pintype "passive"))
      (node (ref "Q1") (pin "G2") (pinfunction "G_G2") (pintype "passive"))
      (node (ref "R1") (pin "2") (pinfunction "2_2") (pintype "passive"))
      (node (ref "R6") (pin "1") (pinfunction "1_1") (pintype "passive"))
    )
    (net (code "16") (name "Net-(Q1A-G)") (class "Default")
      (node (ref "Q1") (pin "G1") (pinfunction "G_G1") (pintype "passive"))
      (node (ref "R2") (pin "2") (pinfunction "2_2") (pintype "passive"))
      (node (ref "R7") (pin "2") (pinfunction "2_2") (pintype "passive"))
    )
    (net (code "17") (name "Net-(Q2A-S)") (class "Default")
      (node (ref "Q2") (pin "S1") (pinfunction "S_S1") (pintype "passive"))
      (node (ref "Q2") (pin "S2") (pinfunction "S_S2") (pintype "passive"))
      (node (ref "R8") (pin "2") (pinfunction "2_2") (pintype "passive"))
    )
    (net (code "18") (name "Net-(Q4B-D)") (class "Default")
      (node (ref "Q4") (pin "D2") (pinfunction "D_D2") (pintype "passive"))
      (node (ref "Q5") (pin "G1") (pinfunction "G_G1") (pintype "passive"))
      (node (ref "Q5") (pin "G2") (pinfunction "G_G2") (pintype "passive"))
      (node (ref "R14") (pin "1") (pinfunction "1_1") (pintype "passive"))
    )
    (net (code "19") (name "Net-(Q4B-G)") (class "Default")
      (node (ref "C6") (pin "1") (pinfunction "1_1") (pintype "passive"))
      (node (ref "Q4") (pin "G2") (pinfunction "G_G2") (pintype "passive"))
      (node (ref "R11") (pin "1") (pinfunction "1_1") (pintype "passive"))
      (node (ref "R12") (pin "2") (pinfunction "2_2") (pintype "passive"))
    )
    (net (code "20") (name "Net-(Q5A-S)") (class "Default")
      (node (ref "Q5") (pin "S1") (pinfunction "S_S1") (pintype "passive"))
      (node (ref "Q5") (pin "S2") (pinfunction "S_S2") (pintype "passive"))
      (node (ref "R14") (pin "2") (pinfunction "2_2") (pintype "passive"))
    )
    (net (code "21") (name "Net-(Q6A-D)") (class "Default")
      (node (ref "Q6") (pin "D1") (pinfunction "D_D1") (pintype "passive"))
      (node (ref "R18") (pin "1") (pinfunction "1_1") (pintype "passive"))
    )
    (net (code "22") (name "Net-(Q6B-D)") (class "Default")
      (node (ref "Q6") (pin "D2") (pinfunction "D_D2") (pintype "passive"))
      (node (ref "R17") (pin "1") (pinfunction "1_1") (pintype "passive"))
    )
    (net (code "23") (name "Net-(TP1-P$1)") (class "Default")
      (node (ref "DL2") (pin "C") (pinfunction "C_C") (pintype "passive"))
      (node (ref "TP1") (pin "1") (pinfunction "P$1_1") (pintype "passive"))
      (node (ref "U1") (pin "2") (pinfunction "STAT_2") (pintype "open_collector"))
    )
    (net (code "24") (name "Net-(TP2-P$1)") (class "Default")
      (node (ref "TP2") (pin "1") (pinfunction "P$1_1") (pintype "passive"))
      (node (ref "U1") (pin "5") (pinfunction "CE_5") (pintype "input"))
    )
    (net (code "25") (name "Net-(TP3-P$1)") (class "Default")
      (node (ref "C3") (pin "1") (pinfunction "1_1") (pintype "passive"))
      (node (ref "F1") (pin "2") (pinfunction "2_2") (pintype "passive"))
      (node (ref "Q3") (pin "D") (pinfunction "D_D") (pintype "passive"))
      (node (ref "Q3") (pin "D2") (pinfunction "D_D2") (pintype "passive"))
      (node (ref "TP3") (pin "1") (pinfunction "P$1_1") (pintype "passive"))
      (node (ref "U1") (pin "3") (pinfunction "VBAT_3") (pintype "power_in"))
    )
    (net (code "26") (name "Net-(TP4-P$1)") (class "Default")
      (node (ref "C8") (pin "1") (pinfunction "1_1") (pintype "passive"))
      (node (ref "Q3") (pin "K") (pinfunction "C_K") (pintype "passive"))
      (node (ref "Q3") (pin "K2") (pinfunction "C_K2") (pintype "passive"))
      (node (ref "Q3") (pin "S") (pinfunction "S_S") (pintype "passive"))
      (node (ref "TP4") (pin "1") (pinfunction "P$1_1") (pintype "passive"))
      (node (ref "U2") (pin "2") (pinfunction "VIN_2") (pintype "power_in"))
    )
    (net (code "27") (name "Net-(TP5-P$1)") (class "Default")
      (node (ref "TP5") (pin "1") (pinfunction "P$1_1") (pintype "passive"))
      (node (ref "U3") (pin "P45") (pinfunction "WIFI_GPIO15_P45") (pintype "bidirectional"))
    )
    (net (code "28") (name "Net-(TP6-P$1)") (class "Default")
      (node (ref "TP6") (pin "1") (pinfunction "P$1_1") (pintype "passive"))
      (node (ref "U3") (pin "P46") (pinfunction "WIFI_GPIO16_P46") (pintype "bidirectional"))
    )
    (net (code "29") (name "Net-(TP7-P$1)") (class "Default")
      (node (ref "TP7") (pin "1") (pinfunction "P$1_1") (pintype "passive"))
      (node (ref "U3") (pin "P47") (pinfunction "WIFI_GPIO18_P47") (pintype "bidirectional"))
    )
    (net (code "30") (name "Net-(TP8-P$1)") (class "Default")
      (node (ref "TP8") (pin "1") (pinfunction "P$1_1") (pintype "passive"))
      (node (ref "U3") (pin "P4") (pinfunction "WIFI_CHIP_EN_P4") (pintype "bidirectional"))
    )
    (net (code "31") (name "Net-(TP9-P$1)") (class "Default")
      (node (ref "TP9") (pin "1") (pinfunction "P$1_1") (pintype "passive"))
      (node (ref "U3") (pin "P48") (pinfunction "WIFI_I2C_SCL_P48") (pintype "bidirectional"))
    )
    (net (code "32") (name "Net-(TP10-P$1)") (class "Default")
      (node (ref "TP10") (pin "1") (pinfunction "P$1_1") (pintype "passive"))
      (node (ref "U3") (pin "P3") (pinfunction "UART_RXD_P3") (pintype "bidirectional"))
    )
    (net (code "33") (name "Net-(TP11-P$1)") (class "Default")
      (node (ref "TP11") (pin "1") (pinfunction "P$1_1") (pintype "passive"))
      (node (ref "U3") (pin "P49") (pinfunction "WIFI_I2C_SDA_P49") (pintype "bidirectional"))
    )
    (net (code "34") (name "Net-(TP12-P$1)") (class "Default")
      (node (ref "TP12") (pin "1") (pinfunction "P$1_1") (pintype "passive"))
      (node (ref "U3") (pin "P2") (pinfunction "UART_TXD_P2") (pintype "bidirectional"))
    )
    (net (code "35") (name "Net-(TP13-P$1)") (class "Default")
      (node (ref "TP13") (pin "1") (pinfunction "P$1_1") (pintype "passive"))
      (node (ref "U3") (pin "P50") (pinfunction "WIFI_RESET_N_P50") (pintype "bidirectional"))
    )
    (net (code "36") (name "Net-(U1-PROG)") (class "Default")
      (node (ref "R3") (pin "2") (pinfunction "2_2") (pintype "passive"))
      (node (ref "U1") (pin "6") (pinfunction "PROG_6") (pintype "passive"))
    )
    (net (code "37") (name "Net-(U3A-WIFI_GPIO1{slash}RTC)") (class "Default")
      (node (ref "R24") (pin "1") (pinfunction "1_1") (pintype "passive"))
      (node (ref "U3") (pin "P5") (pinfunction "WIFI_GPIO1/RTC_P5") (pintype "bidirectional"))
    )
    (net (code "38") (name "PA00_XIN32") (class "Default")
      (node (ref "C11") (pin "2") (pinfunction "2_2") (pintype "passive"))
      (node (ref "U3") (pin "P29") (pinfunction "PA00/XIN32_P29") (pintype "bidirectional"))
      (node (ref "Y1") (pin "2") (pinfunction "2_2") (pintype "passive"))
    )
    (net (code "39") (name "PA01_XOUT32") (class "Default")
      (node (ref "C9") (pin "2") (pinfunction "2_2") (pintype "passive"))
      (node (ref "U3") (pin "P30") (pinfunction "PA01/XOUT32_P30") (pintype "bidirectional"))
      (node (ref "Y1") (pin "1") (pinfunction "1_1") (pintype "passive"))
    )
    (net (code "40") (name "PA02_AIN0") (class "Default")
      (node (ref "J4") (pin "2") (pinfunction "2_2") (pintype "passive"))
      (node (ref "U3") (pin "P31") (pinfunction "PA02_P31") (pintype "bidirectional"))
    )
    (net (code "41") (name "PA03_VREFA") (class "Default")
      (node (ref "C12") (pin "1") (pinfunction "1_1") (pintype "passive"))
      (node (ref "C14") (pin "1") (pinfunction "1_1") (pintype "passive"))
      (node (ref "J4") (pin "1") (pinfunction "1_1") (pintype "passive"))
      (node (ref "U3") (pin "P33") (pinfunction "PA03_P33") (pintype "bidirectional"))
    )
    (net (code "42") (name "PA04_AIN4") (class "Default")
      (node (ref "J4") (pin "5") (pinfunction "5_5") (pintype "passive"))
      (node (ref "U3") (pin "P34") (pinfunction "PA04_P34") (pintype "bidirectional"))
    )
    (net (code "43") (name "PA05_AIN5") (class "Default")
      (node (ref "J4") (pin "6") (pinfunction "6_6") (pintype "passive"))
      (node (ref "U3") (pin "P35") (pinfunction "PA05_P35") (pintype "bidirectional"))
    )
    (net (code "44") (name "PA06_AIN6") (class "Default")
      (node (ref "J4") (pin "7") (pinfunction "7_7") (pintype "passive"))
      (node (ref "U3") (pin "P36") (pinfunction "PA06_P36") (pintype "bidirectional"))
    )
    (net (code "45") (name "PA07_AIN7") (class "Default")
      (node (ref "J4") (pin "8") (pinfunction "8_8") (pintype "passive"))
      (node (ref "U3") (pin "P37") (pinfunction "PA07_P37") (pintype "bidirectional"))
    )
    (net (code "46") (name "PA08_S0_I2C_SDA") (class "Default")
      (node (ref "J5") (pin "6") (pinfunction "6_6") (pintype "passive"))
      (node (ref "R23") (pin "1") (pinfunction "1_1") (pintype "passive"))
      (node (ref "U3") (pin "P38") (pinfunction "PA08_P38") (pintype "bidirectional"))
    )
    (net (code "47") (name "PA09_S0_I2C_SCL") (class "Default")
      (node (ref "J5") (pin "7") (pinfunction "7_7") (pintype "passive"))
      (node (ref "R22") (pin "1") (pinfunction "1_1") (pintype "passive"))
      (node (ref "U3") (pin "P39") (pinfunction "PA09_P39") (pintype "bidirectional"))
    )
    (net (code "48") (name "PA10_TCC0-W2") (class "Default")
      (node (ref "J4") (pin "11") (pinfunction "11_11") (pintype "passive"))
      (node (ref "U3") (pin "P40") (pinfunction "PA10_P40") (pintype "bidirectional"))
    )
    (net (code "49") (name "PA11_TCC0-W3") (class "Default")
      (node (ref "J4") (pin "12") (pinfunction "12_12") (pintype "passive"))
      (node (ref "U3") (pin "P41") (pinfunction "PA11_P41") (pintype "bidirectional"))
    )
    (net (code "50") (name "PA16_S1_MOSI") (class "Default")
      (node (ref "J5") (pin "3") (pinfunction "3_3") (pintype "passive"))
      (node (ref "U3") (pin "P8") (pinfunction "PA16_P8") (pintype "bidirectional"))
    )
    (net (code "51") (name "PA17_S1_SCK") (class "Default")
      (node (ref "J5") (pin "4") (pinfunction "4_4") (pintype "passive"))
      (node (ref "U3") (pin "P9") (pinfunction "PA17_P9") (pintype "bidirectional"))
    )
    (net (code "52") (name "PA18_USB_ID") (class "Default")
      (node (ref "R9") (pin "2") (pinfunction "2_2") (pintype "passive"))
      (node (ref "U3") (pin "P11") (pinfunction "PA18_P11") (pintype "bidirectional"))
    )
    (net (code "53") (name "PA19_S1_MISO") (class "Default")
      (node (ref "J5") (pin "5") (pinfunction "5_5") (pintype "passive"))
      (node (ref "U3") (pin "P12") (pinfunction "PA19_P12") (pintype "bidirectional"))
    )
    (net (code "54") (name "PA20_TCC0-W6") (class "Default")
      (node (ref "J5") (pin "1") (pinfunction "1_1") (pintype "passive"))
      (node (ref "Q6") (pin "G1") (pinfunction "G_G1") (pintype "passive"))
      (node (ref "R21") (pin "2") (pinfunction "2_2") (pintype "passive"))
      (node (ref "U3") (pin "P13") (pinfunction "PA20_P13") (pintype "bidirectional"))
    )
    (net (code "55") (name "PA21_TCC0-W7") (class "Default")
      (node (ref "J5") (pin "2") (pinfunction "2_2") (pintype "passive"))
      (node (ref "Q6") (pin "G2") (pinfunction "G_G2") (pintype "passive"))
      (node (ref "R19") (pin "2") (pinfunction "2_2") (pintype "passive"))
      (node (ref "U3") (pin "P14") (pinfunction "PA21_P14") (pintype "bidirectional"))
    )
    (net (code "56") (name "PA22_TC4-W0") (class "Default")
      (node (ref "J4") (pin "9") (pinfunction "9_9") (pintype "passive"))
      (node (ref "U3") (pin "P15") (pinfunction "PA22_P15") (pintype "bidirectional"))
    )
    (net (code "57") (name "PA23_TC4-W1") (class "Default")
      (node (ref "J4") (pin "10") (pinfunction "10_10") (pintype "passive"))
      (node (ref "U3") (pin "P16") (pinfunction "PA23_P16") (pintype "bidirectional"))
    )
    (net (code "58") (name "PA30_SWCLK") (class "Default")
      (node (ref "J3") (pin "4") (pinfunction "4_4") (pintype "passive"))
      (node (ref "U3") (pin "P25") (pinfunction "PA30/SWCLK_P25") (pintype "bidirectional"))
    )
    (net (code "59") (name "PA31_SWDIO") (class "Default")
      (node (ref "J3") (pin "2") (pinfunction "2_2") (pintype "passive"))
      (node (ref "U3") (pin "P26") (pinfunction "PA31/SWDIO_P26") (pintype "bidirectional"))
    )
    (net (code "60") (name "PB02_AIN10") (class "Default")
      (node (ref "J4") (pin "3") (pinfunction "3_3") (pintype "passive"))
      (node (ref "U3") (pin "P27") (pinfunction "PB02_P27") (pintype "bidirectional"))
    )
    (net (code "61") (name "PB03_AIN11") (class "Default")
      (node (ref "J4") (pin "4") (pinfunction "4_4") (pintype "passive"))
      (node (ref "U3") (pin "P28") (pinfunction "PB03_P28") (pintype "bidirectional"))
    )
    (net (code "62") (name "PB10_TCC0-W4") (class "Default")
      (node (ref "J4") (pin "13") (pinfunction "13_13") (pintype "passive"))
      (node (ref "U3") (pin "P43") (pinfunction "PB10_P43") (pintype "bidirectional"))
    )
    (net (code "63") (name "PB11_TCC0-W5") (class "Default")
      (node (ref "J4") (pin "14") (pinfunction "14_14") (pintype "passive"))
      (node (ref "R24") (pin "2") (pinfunction "2_2") (pintype "passive"))
      (node (ref "U3") (pin "P44") (pinfunction "PB11_P44") (pintype "bidirectional"))
    )
    (net (code "64") (name "PB22_S5_TX") (class "Default")
      (node (ref "J5") (pin "9") (pinfunction "9_9") (pintype "passive"))
      (node (ref "U3") (pin "P22") (pinfunction "PB22_P22") (pintype "bidirectional"))
    )
    (net (code "65") (name "PB23_S5_RX") (class "Default")
      (node (ref "J5") (pin "8") (pinfunction "8_8") (pintype "passive"))
      (node (ref "U3") (pin "P23") (pinfunction "PB23_P23") (pintype "bidirectional"))
    )
    (net (code "66") (name "RESET#") (class "Default")
      (node (ref "J5") (pin "10") (pinfunction "10_10") (pintype "passive"))
      (node (ref "R20") (pin "2") (pinfunction "2_2") (pintype "passive"))
    )
    (net (code "67") (name "RESETN") (class "Default")
      (node (ref "C7") (pin "1") (pinfunction "1_1") (pintype "passive"))
      (node (ref "R13") (pin "2") (pinfunction "2_2") (pintype "passive"))
      (node (ref "R15") (pin "2") (pinfunction "2_2") (pintype "passive"))
      (node (ref "R16") (pin "2") (pinfunction "2_2") (pintype "passive"))
      (node (ref "R20") (pin "1") (pinfunction "1_1") (pintype "passive"))
      (node (ref "U3") (pin "P24") (pinfunction "RESET_N_P24") (pintype "bidirectional"))
    )
    (net (code "68") (name "USB_ID") (class "Default")
      (node (ref "J1") (pin "4") (pinfunction "4_4") (pintype "passive"))
      (node (ref "Q1") (pin "D2") (pinfunction "D_D2") (pintype "passive"))
      (node (ref "Q2") (pin "G1") (pinfunction "G_G1") (pintype "passive"))
      (node (ref "Q2") (pin "G2") (pinfunction "G_G2") (pintype "passive"))
      (node (ref "R8") (pin "1") (pinfunction "1_1") (pintype "passive"))
      (node (ref "R9") (pin "1") (pinfunction "1_1") (pintype "passive"))
    )
    (net (code "69") (name "VIN") (class "Default")
      (node (ref "J5") (pin "13") (pinfunction "13_13") (pintype "passive"))
      (node (ref "Q5") (pin "D1") (pinfunction "D_D1") (pintype "passive"))
      (node (ref "Q5") (pin "D1'") (pinfunction "D_D1'") (pintype "passive"))
      (node (ref "R11") (pin "2") (pinfunction "2_2") (pintype "passive"))
      (node (ref "R7") (pin "1") (pinfunction "1_1") (pintype "passive"))
    )
    (net (code "70") (name "VUSB") (class "Default")
      (node (ref "C5") (pin "1") (pinfunction "1_1") (pintype "passive"))
      (node (ref "L2") (pin "2") (pinfunction "2_2") (pintype "passive"))
      (node (ref "Q2") (pin "D1") (pinfunction "D_D1") (pintype "passive"))
      (node (ref "Q2") (pin "D1'") (pinfunction "D_D1'") (pintype "passive"))
      (node (ref "R6") (pin "2") (pinfunction "2_2") (pintype "passive"))
    )
    (net (code "71") (name "unconnected-(J3-Pad6)") (class "Default")
      (node (ref "J3") (pin "6") (pinfunction "6_6") (pintype "passive"))
    )
    (net (code "72") (name "unconnected-(J3-Pad7)") (class "Default")
      (node (ref "J3") (pin "7") (pinfunction "7_7") (pintype "passive"))
    )
    (net (code "73") (name "unconnected-(J3-Pad8)") (class "Default")
      (node (ref "J3") (pin "8") (pinfunction "8_8") (pintype "passive"))
    )
    (net (code "74") (name "unconnected-(Q4A-D-PadD1)") (class "Default")
      (node (ref "Q4") (pin "D1") (pinfunction "D_D1") (pintype "passive"))
    )
    (net (code "75") (name "unconnected-(U3A-NC-PadP6)") (class "Default")
      (node (ref "U3") (pin "P6") (pinfunction "NC_P6") (pintype "bidirectional"))
    )
  )
)
